# InputSel.net
KiCad netlist of a schematic drawn in EAGLE
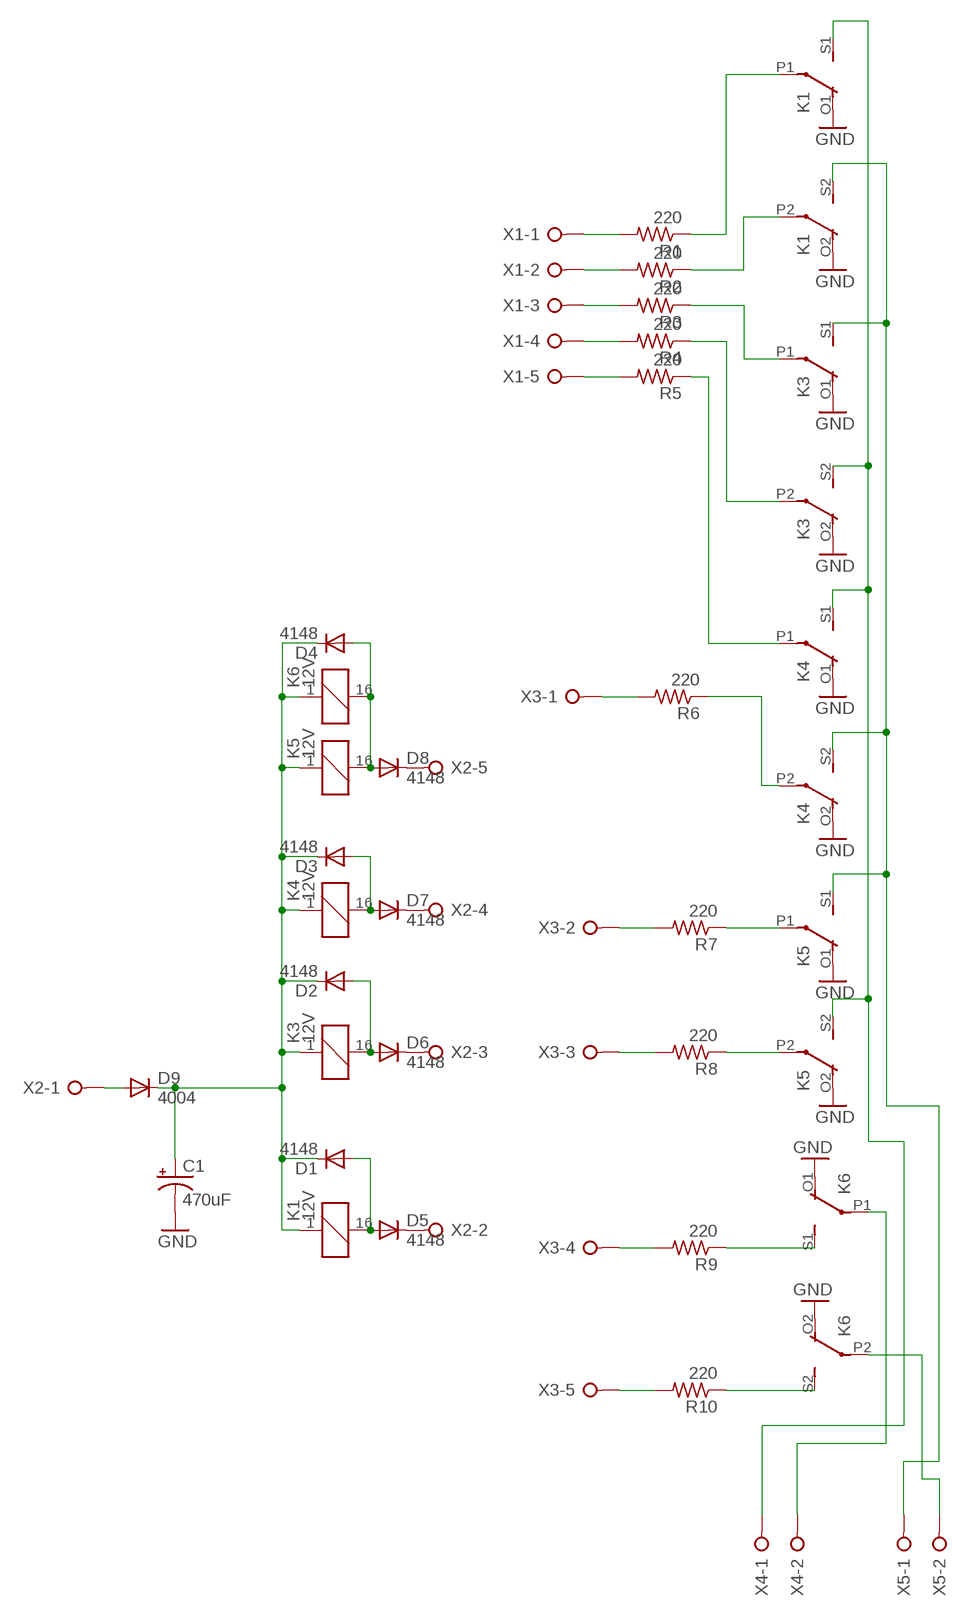
[diagram p0: schematic, sheet 1]

(export (version "E")
  (design (tool "Eeschema 10.0.6"))
  (components
    (comp (ref "C1")
      (value "470uF")
      (footprint "eagle-import:E5-10,5")
      (libsource (lib "eagle-import") (part "CPOL-USE5-10.5"))
    )
    (comp (ref "D1")
      (value "4148")
      (footprint "eagle-import:DO35-7")
      (libsource (lib "eagle-import") (part "1N4148DO35-7"))
    )
    (comp (ref "D2")
      (value "4148")
      (footprint "eagle-import:DO35-7")
      (libsource (lib "eagle-import") (part "1N4148DO35-7"))
    )
    (comp (ref "D3")
      (value "4148")
      (footprint "eagle-import:DO35-7")
      (libsource (lib "eagle-import") (part "1N4148DO35-7"))
    )
    (comp (ref "D4")
      (value "4148")
      (footprint "eagle-import:DO35-7")
      (libsource (lib "eagle-import") (part "1N4148DO35-7"))
    )
    (comp (ref "D5")
      (value "4148")
      (footprint "eagle-import:DO35-7")
      (libsource (lib "eagle-import") (part "1N4148DO35-7"))
    )
    (comp (ref "D6")
      (value "4148")
      (footprint "eagle-import:DO35-7")
      (libsource (lib "eagle-import") (part "1N4148DO35-7"))
    )
    (comp (ref "D7")
      (value "4148")
      (footprint "eagle-import:DO35-7")
      (libsource (lib "eagle-import") (part "1N4148DO35-7"))
    )
    (comp (ref "D8")
      (value "4148")
      (footprint "eagle-import:DO35-7")
      (libsource (lib "eagle-import") (part "1N4148DO35-7"))
    )
    (comp (ref "D9")
      (value "4004")
      (footprint "eagle-import:DO35-10")
      (libsource (lib "eagle-import") (part "1N4148DO35-10"))
    )
    (comp (ref "K1")
      (value "12V")
      (footprint "eagle-import:G6A-234P")
      (libsource (lib "eagle-import") (part "G6A-234P"))
    )
    (comp (ref "K3")
      (value "12V")
      (footprint "eagle-import:G6A-234P")
      (fields (field (name "OC_FARNELL") "unknown") (field (name "OC_NEWARK") "unknown"))
      (libsource (lib "eagle-import") (part "G6A-234P"))
    )
    (comp (ref "K4")
      (value "12V")
      (footprint "eagle-import:G6A-234P")
      (fields (field (name "OC_FARNELL") "unknown") (field (name "OC_NEWARK") "unknown"))
      (libsource (lib "eagle-import") (part "G6A-234P"))
    )
    (comp (ref "K5")
      (value "12V")
      (footprint "eagle-import:G6A-234P")
      (fields (field (name "OC_FARNELL") "unknown") (field (name "OC_NEWARK") "unknown"))
      (libsource (lib "eagle-import") (part "G6A-234P"))
    )
    (comp (ref "K6")
      (value "12V")
      (footprint "eagle-import:G6A-234P")
      (fields (field (name "OC_FARNELL") "unknown") (field (name "OC_NEWARK") "unknown"))
      (libsource (lib "eagle-import") (part "G6A-234P"))
    )
    (comp (ref "R1")
      (value "220")
      (footprint "eagle-import:0207_10")
      (libsource (lib "eagle-import") (part "R-US_0207/10"))
    )
    (comp (ref "R2")
      (value "220")
      (footprint "eagle-import:0207_10")
      (libsource (lib "eagle-import") (part "R-US_0207/10"))
    )
    (comp (ref "R3")
      (value "220")
      (footprint "eagle-import:0207_10")
      (libsource (lib "eagle-import") (part "R-US_0207/10"))
    )
    (comp (ref "R4")
      (value "220")
      (footprint "eagle-import:0207_10")
      (libsource (lib "eagle-import") (part "R-US_0207/10"))
    )
    (comp (ref "R5")
      (value "220")
      (footprint "eagle-import:0207_10")
      (libsource (lib "eagle-import") (part "R-US_0207/10"))
    )
    (comp (ref "R6")
      (value "220")
      (footprint "eagle-import:0207_10")
      (libsource (lib "eagle-import") (part "R-US_0207/10"))
    )
    (comp (ref "R7")
      (value "220")
      (footprint "eagle-import:0207_10")
      (libsource (lib "eagle-import") (part "R-US_0207/10"))
    )
    (comp (ref "R8")
      (value "220")
      (footprint "eagle-import:0207_10")
      (libsource (lib "eagle-import") (part "R-US_0207/10"))
    )
    (comp (ref "R9")
      (value "220")
      (footprint "eagle-import:0207_10")
      (libsource (lib "eagle-import") (part "R-US_0207/10"))
    )
    (comp (ref "R10")
      (value "220")
      (footprint "eagle-import:0207_10")
      (libsource (lib "eagle-import") (part "R-US_0207/10"))
    )
    (comp (ref "X1")
      (value "W237-05P")
      (footprint "eagle-import:W237-5P")
      (libsource (lib "eagle-import") (part "W237-05P"))
    )
    (comp (ref "X2")
      (value "W237-05P")
      (footprint "eagle-import:W237-5P")
      (fields (field (name "OC_FARNELL") "unknown") (field (name "OC_NEWARK") "unknown"))
      (libsource (lib "eagle-import") (part "W237-05P"))
    )
    (comp (ref "X3")
      (value "W237-05P")
      (footprint "eagle-import:W237-5P")
      (libsource (lib "eagle-import") (part "W237-05P"))
    )
    (comp (ref "X4")
      (value "W237-02P")
      (footprint "eagle-import:W237-132")
      (fields (field (name "OC_FARNELL") "unknown") (field (name "OC_NEWARK") "unknown"))
      (libsource (lib "eagle-import") (part "W237-02P"))
    )
    (comp (ref "X5")
      (value "W237-02P")
      (footprint "eagle-import:W237-132")
      (fields (field (name "OC_FARNELL") "unknown") (field (name "OC_NEWARK") "unknown"))
      (libsource (lib "eagle-import") (part "W237-02P"))
    )
  )
  (nets
    (net (code "1") (name "GND") (class "Default")
      (node (ref "C1") (pin "-") (pinfunction "-_-") (pintype "passive"))
      (node (ref "K1") (pin "O1") (pinfunction "O_O1") (pintype "passive"))
      (node (ref "K1") (pin "O2") (pinfunction "O_O2") (pintype "passive"))
      (node (ref "K3") (pin "O1") (pinfunction "O_O1") (pintype "passive"))
      (node (ref "K3") (pin "O2") (pinfunction "O_O2") (pintype "passive"))
      (node (ref "K4") (pin "O1") (pinfunction "O_O1") (pintype "passive"))
      (node (ref "K4") (pin "O2") (pinfunction "O_O2") (pintype "passive"))
      (node (ref "K5") (pin "O1") (pinfunction "O_O1") (pintype "passive"))
      (node (ref "K5") (pin "O2") (pinfunction "O_O2") (pintype "passive"))
      (node (ref "K6") (pin "O1") (pinfunction "O_O1") (pintype "passive"))
      (node (ref "K6") (pin "O2") (pinfunction "O_O2") (pintype "passive"))
    )
    (net (code "2") (name "Net-(C1-Pad+)") (class "Default")
      (node (ref "C1") (pin "+") (pinfunction "+_+") (pintype "passive"))
      (node (ref "D1") (pin "C") (pinfunction "C_C") (pintype "passive"))
      (node (ref "D2") (pin "C") (pinfunction "C_C") (pintype "passive"))
      (node (ref "D3") (pin "C") (pinfunction "C_C") (pintype "passive"))
      (node (ref "D4") (pin "C") (pinfunction "C_C") (pintype "passive"))
      (node (ref "D9") (pin "C") (pinfunction "C_C") (pintype "passive"))
      (node (ref "K1") (pin "1") (pinfunction "1_1") (pintype "passive"))
      (node (ref "K3") (pin "1") (pinfunction "1_1") (pintype "passive"))
      (node (ref "K4") (pin "1") (pinfunction "1_1") (pintype "passive"))
      (node (ref "K5") (pin "1") (pinfunction "1_1") (pintype "passive"))
      (node (ref "K6") (pin "1") (pinfunction "1_1") (pintype "passive"))
    )
    (net (code "3") (name "Net-(K1A-2)") (class "Default")
      (node (ref "D1") (pin "A") (pinfunction "A_A") (pintype "passive"))
      (node (ref "D5") (pin "A") (pinfunction "A_A") (pintype "passive"))
      (node (ref "K1") (pin "16") (pinfunction "2_16") (pintype "passive"))
    )
    (net (code "4") (name "Net-(K1B-P)") (class "Default")
      (node (ref "K1") (pin "P1") (pinfunction "P_P1") (pintype "passive"))
      (node (ref "R1") (pin "1") (pinfunction "1_1") (pintype "passive"))
    )
    (net (code "5") (name "Net-(K1B-S)") (class "Default")
      (node (ref "K1") (pin "S1") (pinfunction "S_S1") (pintype "passive"))
      (node (ref "K3") (pin "S2") (pinfunction "S_S2") (pintype "passive"))
      (node (ref "K4") (pin "S1") (pinfunction "S_S1") (pintype "passive"))
      (node (ref "K5") (pin "S2") (pinfunction "S_S2") (pintype "passive"))
      (node (ref "X4") (pin "1") (pinfunction "KL_1") (pintype "passive"))
    )
    (net (code "6") (name "Net-(K1C-P)") (class "Default")
      (node (ref "K1") (pin "P2") (pinfunction "P_P2") (pintype "passive"))
      (node (ref "R2") (pin "1") (pinfunction "1_1") (pintype "passive"))
    )
    (net (code "7") (name "Net-(K1C-S)") (class "Default")
      (node (ref "K1") (pin "S2") (pinfunction "S_S2") (pintype "passive"))
      (node (ref "K3") (pin "S1") (pinfunction "S_S1") (pintype "passive"))
      (node (ref "K4") (pin "S2") (pinfunction "S_S2") (pintype "passive"))
      (node (ref "K5") (pin "S1") (pinfunction "S_S1") (pintype "passive"))
      (node (ref "X5") (pin "1") (pinfunction "KL_1") (pintype "passive"))
    )
    (net (code "8") (name "Net-(K3A-2)") (class "Default")
      (node (ref "D2") (pin "A") (pinfunction "A_A") (pintype "passive"))
      (node (ref "D6") (pin "A") (pinfunction "A_A") (pintype "passive"))
      (node (ref "K3") (pin "16") (pinfunction "2_16") (pintype "passive"))
    )
    (net (code "9") (name "Net-(K3B-P)") (class "Default")
      (node (ref "K3") (pin "P1") (pinfunction "P_P1") (pintype "passive"))
      (node (ref "R3") (pin "1") (pinfunction "1_1") (pintype "passive"))
    )
    (net (code "10") (name "Net-(K3C-P)") (class "Default")
      (node (ref "K3") (pin "P2") (pinfunction "P_P2") (pintype "passive"))
      (node (ref "R4") (pin "1") (pinfunction "1_1") (pintype "passive"))
    )
    (net (code "11") (name "Net-(K4A-2)") (class "Default")
      (node (ref "D3") (pin "A") (pinfunction "A_A") (pintype "passive"))
      (node (ref "D7") (pin "A") (pinfunction "A_A") (pintype "passive"))
      (node (ref "K4") (pin "16") (pinfunction "2_16") (pintype "passive"))
    )
    (net (code "12") (name "Net-(K4B-P)") (class "Default")
      (node (ref "K4") (pin "P1") (pinfunction "P_P1") (pintype "passive"))
      (node (ref "R5") (pin "1") (pinfunction "1_1") (pintype "passive"))
    )
    (net (code "13") (name "Net-(K4C-P)") (class "Default")
      (node (ref "K4") (pin "P2") (pinfunction "P_P2") (pintype "passive"))
      (node (ref "R6") (pin "1") (pinfunction "1_1") (pintype "passive"))
    )
    (net (code "14") (name "Net-(K5A-2)") (class "Default")
      (node (ref "D4") (pin "A") (pinfunction "A_A") (pintype "passive"))
      (node (ref "D8") (pin "A") (pinfunction "A_A") (pintype "passive"))
      (node (ref "K5") (pin "16") (pinfunction "2_16") (pintype "passive"))
      (node (ref "K6") (pin "16") (pinfunction "2_16") (pintype "passive"))
    )
    (net (code "15") (name "Net-(K5B-P)") (class "Default")
      (node (ref "K5") (pin "P1") (pinfunction "P_P1") (pintype "passive"))
      (node (ref "R7") (pin "1") (pinfunction "1_1") (pintype "passive"))
    )
    (net (code "16") (name "Net-(K5C-P)") (class "Default")
      (node (ref "K5") (pin "P2") (pinfunction "P_P2") (pintype "passive"))
      (node (ref "R8") (pin "1") (pinfunction "1_1") (pintype "passive"))
    )
    (net (code "17") (name "Net-(K6B-P)") (class "Default")
      (node (ref "K6") (pin "P1") (pinfunction "P_P1") (pintype "passive"))
      (node (ref "X4") (pin "2") (pinfunction "KL_2") (pintype "passive"))
    )
    (net (code "18") (name "Net-(K6B-S)") (class "Default")
      (node (ref "K6") (pin "S1") (pinfunction "S_S1") (pintype "passive"))
      (node (ref "R9") (pin "1") (pinfunction "1_1") (pintype "passive"))
    )
    (net (code "19") (name "Net-(K6C-P)") (class "Default")
      (node (ref "K6") (pin "P2") (pinfunction "P_P2") (pintype "passive"))
      (node (ref "X5") (pin "2") (pinfunction "KL_2") (pintype "passive"))
    )
    (net (code "20") (name "Net-(K6C-S)") (class "Default")
      (node (ref "K6") (pin "S2") (pinfunction "S_S2") (pintype "passive"))
      (node (ref "R10") (pin "1") (pinfunction "1_1") (pintype "passive"))
    )
    (net (code "21") (name "Net-(X1A-KL)") (class "Default")
      (node (ref "R1") (pin "2") (pinfunction "2_2") (pintype "passive"))
      (node (ref "X1") (pin "1") (pinfunction "KL_1") (pintype "passive"))
    )
    (net (code "22") (name "Net-(X1B-KL)") (class "Default")
      (node (ref "R2") (pin "2") (pinfunction "2_2") (pintype "passive"))
      (node (ref "X1") (pin "2") (pinfunction "KL_2") (pintype "passive"))
    )
    (net (code "23") (name "Net-(X1C-KL)") (class "Default")
      (node (ref "R3") (pin "2") (pinfunction "2_2") (pintype "passive"))
      (node (ref "X1") (pin "3") (pinfunction "KL_3") (pintype "passive"))
    )
    (net (code "24") (name "Net-(X1D-KL)") (class "Default")
      (node (ref "R4") (pin "2") (pinfunction "2_2") (pintype "passive"))
      (node (ref "X1") (pin "4") (pinfunction "KL_4") (pintype "passive"))
    )
    (net (code "25") (name "Net-(X1E-KL)") (class "Default")
      (node (ref "R5") (pin "2") (pinfunction "2_2") (pintype "passive"))
      (node (ref "X1") (pin "5") (pinfunction "KL_5") (pintype "passive"))
    )
    (net (code "26") (name "Net-(X2A-KL)") (class "Default")
      (node (ref "D9") (pin "A") (pinfunction "A_A") (pintype "passive"))
      (node (ref "X2") (pin "1") (pinfunction "KL_1") (pintype "passive"))
    )
    (net (code "27") (name "Net-(X2B-KL)") (class "Default")
      (node (ref "D5") (pin "C") (pinfunction "C_C") (pintype "passive"))
      (node (ref "X2") (pin "2") (pinfunction "KL_2") (pintype "passive"))
    )
    (net (code "28") (name "Net-(X2C-KL)") (class "Default")
      (node (ref "D6") (pin "C") (pinfunction "C_C") (pintype "passive"))
      (node (ref "X2") (pin "3") (pinfunction "KL_3") (pintype "passive"))
    )
    (net (code "29") (name "Net-(X2D-KL)") (class "Default")
      (node (ref "D7") (pin "C") (pinfunction "C_C") (pintype "passive"))
      (node (ref "X2") (pin "4") (pinfunction "KL_4") (pintype "passive"))
    )
    (net (code "30") (name "Net-(X2E-KL)") (class "Default")
      (node (ref "D8") (pin "C") (pinfunction "C_C") (pintype "passive"))
      (node (ref "X2") (pin "5") (pinfunction "KL_5") (pintype "passive"))
    )
    (net (code "31") (name "Net-(X3A-KL)") (class "Default")
      (node (ref "R6") (pin "2") (pinfunction "2_2") (pintype "passive"))
      (node (ref "X3") (pin "1") (pinfunction "KL_1") (pintype "passive"))
    )
    (net (code "32") (name "Net-(X3B-KL)") (class "Default")
      (node (ref "R7") (pin "2") (pinfunction "2_2") (pintype "passive"))
      (node (ref "X3") (pin "2") (pinfunction "KL_2") (pintype "passive"))
    )
    (net (code "33") (name "Net-(X3C-KL)") (class "Default")
      (node (ref "R8") (pin "2") (pinfunction "2_2") (pintype "passive"))
      (node (ref "X3") (pin "3") (pinfunction "KL_3") (pintype "passive"))
    )
    (net (code "34") (name "Net-(X3D-KL)") (class "Default")
      (node (ref "R9") (pin "2") (pinfunction "2_2") (pintype "passive"))
      (node (ref "X3") (pin "4") (pinfunction "KL_4") (pintype "passive"))
    )
    (net (code "35") (name "Net-(X3E-KL)") (class "Default")
      (node (ref "R10") (pin "2") (pinfunction "2_2") (pintype "passive"))
      (node (ref "X3") (pin "5") (pinfunction "KL_5") (pintype "passive"))
    )
  )
)
